# AFE_Only_ReplacedDischarge.net
KiCad netlist of a schematic drawn in EAGLE
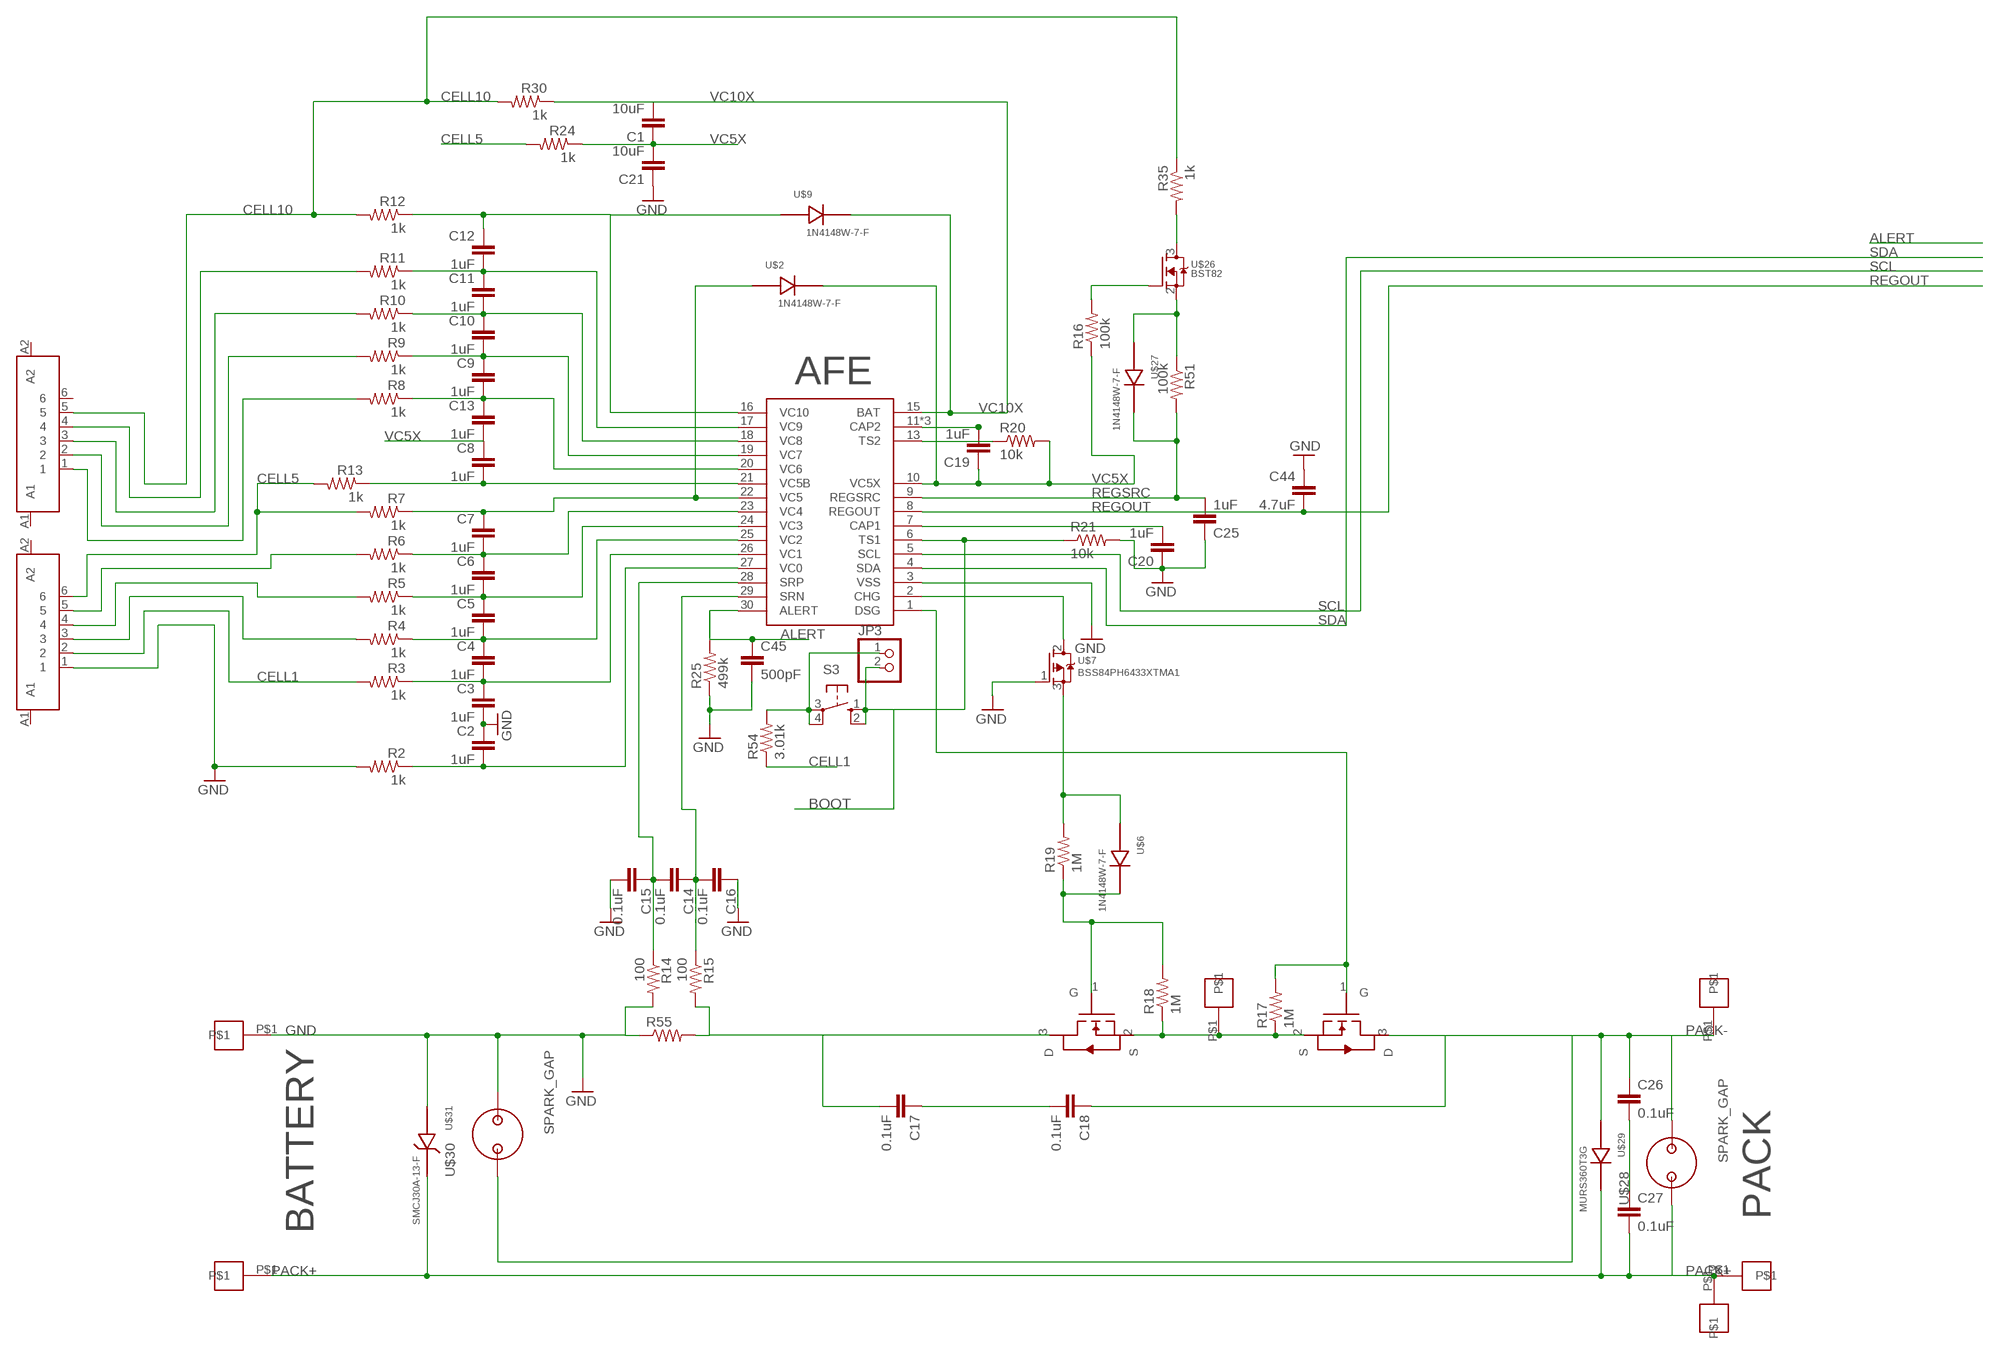
[diagram p0: schematic, sheet 1]
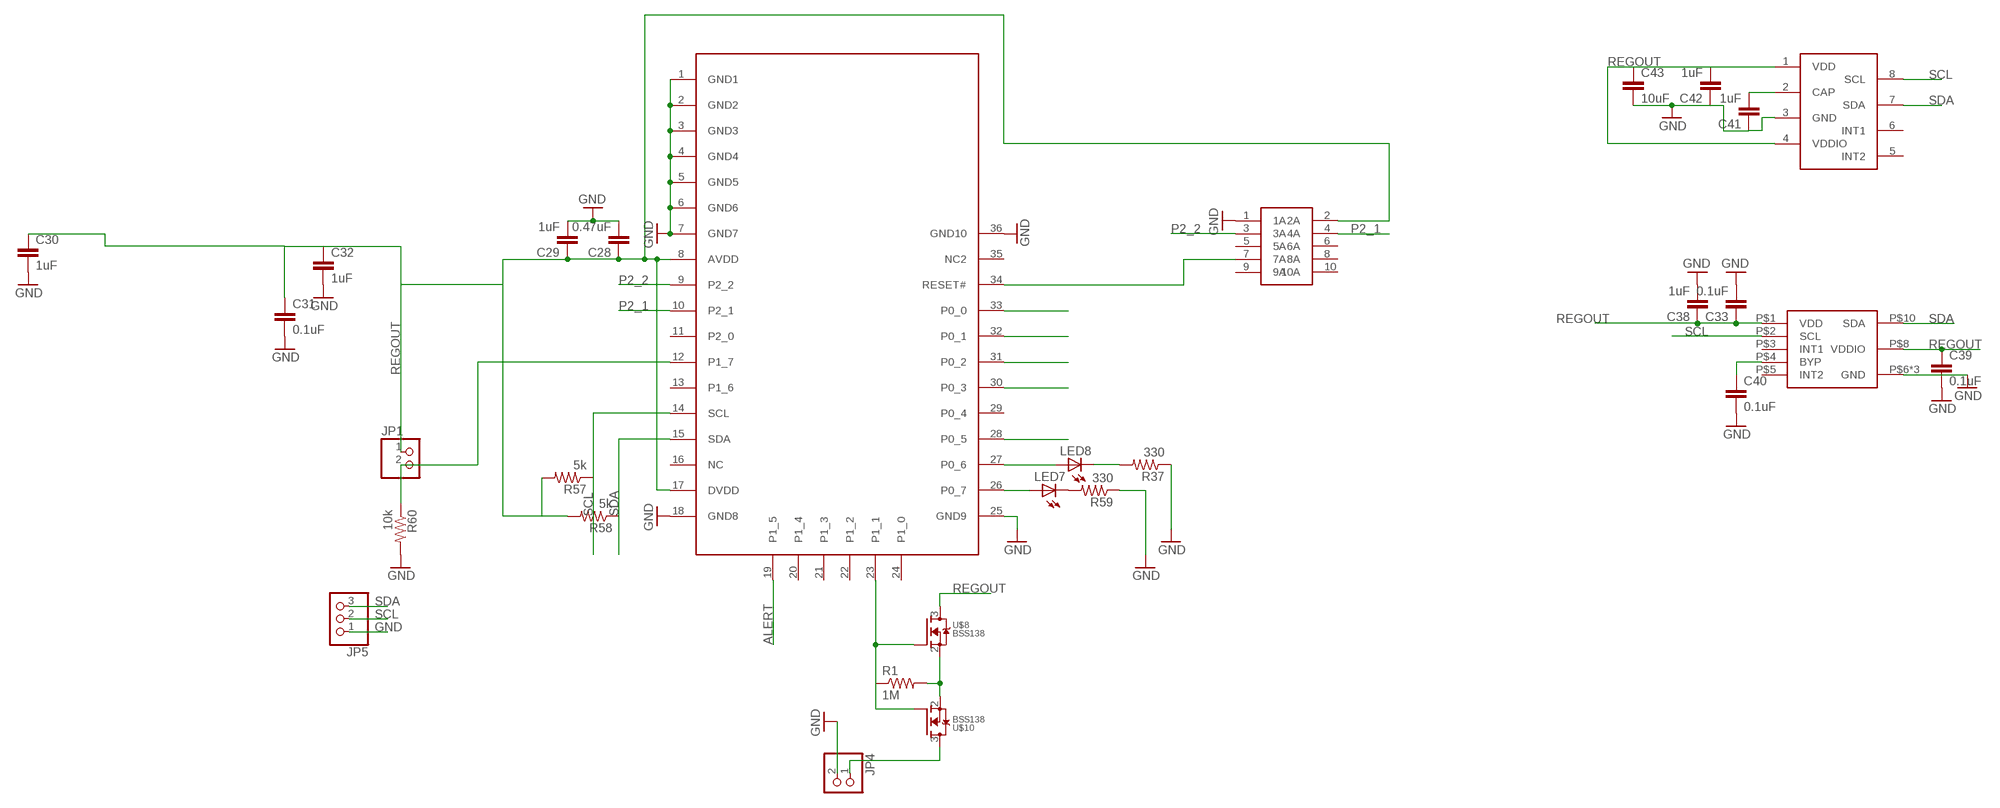
[diagram p1: schematic, sheet 2]

(export (version "E")
  (design (tool "Eeschema 10.0.6"))
  (components
    (comp (ref "C28")
      (value "0.47uF")
      (footprint "eagle-import:C0402")
      (libsource (lib "eagle-import") (part "C-EUC0402"))
    )
    (comp (ref "C29")
      (value "1uF")
      (footprint "eagle-import:C0402")
      (libsource (lib "eagle-import") (part "C-EUC0402"))
    )
    (comp (ref "C30")
      (value "1uF")
      (footprint "eagle-import:C0402")
      (libsource (lib "eagle-import") (part "C-EUC0402"))
    )
    (comp (ref "C31")
      (value "0.1uF")
      (footprint "eagle-import:C0402")
      (libsource (lib "eagle-import") (part "C-EUC0402"))
    )
    (comp (ref "C32")
      (value "1uF")
      (footprint "eagle-import:C0402")
      (libsource (lib "eagle-import") (part "C-EUC0402"))
    )
    (comp (ref "C33")
      (value "0.1uF")
      (footprint "eagle-import:C0402")
      (libsource (lib "eagle-import") (part "C-EUC0402"))
    )
    (comp (ref "C38")
      (value "1uF")
      (footprint "eagle-import:C0402")
      (libsource (lib "eagle-import") (part "C-EUC0402"))
    )
    (comp (ref "C39")
      (value "0.1uF")
      (footprint "eagle-import:C0402")
      (libsource (lib "eagle-import") (part "C-EUC0402"))
    )
    (comp (ref "C40")
      (value "0.1uF")
      (footprint "eagle-import:C0402")
      (libsource (lib "eagle-import") (part "C-EUC0402"))
    )
    (comp (ref "C41")
      (value "1uF")
      (footprint "eagle-import:C0402")
      (libsource (lib "eagle-import") (part "C-EUC0402"))
    )
    (comp (ref "C42")
      (value "1uF")
      (footprint "eagle-import:C0402")
      (libsource (lib "eagle-import") (part "C-EUC0402"))
    )
    (comp (ref "C43")
      (value "10uF")
      (footprint "eagle-import:C0603")
      (libsource (lib "eagle-import") (part "C-EUC0603"))
    )
    (comp (ref "JP1")
      (value "PINHD-1X2")
      (footprint "eagle-import:1X02")
      (libsource (lib "eagle-import") (part "PINHD-1X2"))
    )
    (comp (ref "JP4")
      (value "PINHD-1X2")
      (footprint "eagle-import:1X02")
      (libsource (lib "eagle-import") (part "PINHD-1X2"))
    )
    (comp (ref "JP5")
      (value "PINHD-1X3")
      (footprint "eagle-import:1X03")
      (libsource (lib "eagle-import") (part "PINHD-1X3"))
    )
    (comp (ref "LED7")
      (value "LEDCHIP-LED0603")
      (footprint "eagle-import:CHIP-LED0603")
      (libsource (lib "eagle-import") (part "LEDCHIP-LED0603"))
    )
    (comp (ref "LED8")
      (value "LEDCHIP-LED0603")
      (footprint "eagle-import:CHIP-LED0603")
      (libsource (lib "eagle-import") (part "LEDCHIP-LED0603"))
    )
    (comp (ref "R1")
      (value "1M")
      (footprint "eagle-import:R0402")
      (libsource (lib "eagle-import") (part "R-US_R0402"))
    )
    (comp (ref "R37")
      (value "330")
      (footprint "eagle-import:R0402")
      (libsource (lib "eagle-import") (part "R-US_R0402"))
    )
    (comp (ref "R57")
      (value "5k")
      (footprint "eagle-import:R0402")
      (libsource (lib "eagle-import") (part "R-US_R0402"))
    )
    (comp (ref "R58")
      (value "5k")
      (footprint "eagle-import:R0402")
      (libsource (lib "eagle-import") (part "R-US_R0402"))
    )
    (comp (ref "R59")
      (value "330")
      (footprint "eagle-import:R0402")
      (libsource (lib "eagle-import") (part "R-US_R0402"))
    )
    (comp (ref "R60")
      (value "10k")
      (footprint "eagle-import:R0402")
      (libsource (lib "eagle-import") (part "R-US_R0402"))
    )
    (comp (ref "U$8")
      (value "BSS138")
      (footprint "eagle-import:SOT23-3")
      (libsource (lib "eagle-import") (part "BSS138"))
    )
    (comp (ref "U$10")
      (value "BSS138")
      (footprint "eagle-import:SOT23-3")
      (libsource (lib "eagle-import") (part "BSS138"))
    )
    (comp (ref "U$20")
      (value "BLE113")
      (footprint "eagle-import:BLUEGIGA")
      (libsource (lib "eagle-import") (part "BLE113"))
    )
    (comp (ref "U$22")
      (value "RIBBON_10POS_MALE")
      (footprint "eagle-import:RIBBON_10POS_MALE")
      (libsource (lib "eagle-import") (part "RIBBON_10POS_MALE"))
    )
    (comp (ref "U$25")
      (value "MLP3115A2")
      (footprint "eagle-import:MLP3115A2")
      (libsource (lib "eagle-import") (part "MLP3115A2"))
    )
    (comp (ref "U$32")
      (value "MMA8653FC")
      (footprint "eagle-import:10-DFN2X2")
      (libsource (lib "eagle-import") (part "MMA8653FC"))
    )
    (comp (ref "C1")
      (value "10uF")
      (footprint "eagle-import:C1210")
      (libsource (lib "eagle-import") (part "C-EUC1210"))
    )
    (comp (ref "C2")
      (value "1uF")
      (footprint "eagle-import:C0805")
      (libsource (lib "eagle-import") (part "C-EUC0805"))
    )
    (comp (ref "C3")
      (value "1uF")
      (footprint "eagle-import:C0805")
      (libsource (lib "eagle-import") (part "C-EUC0805"))
    )
    (comp (ref "C4")
      (value "1uF")
      (footprint "eagle-import:C0805")
      (libsource (lib "eagle-import") (part "C-EUC0805"))
    )
    (comp (ref "C5")
      (value "1uF")
      (footprint "eagle-import:C0805")
      (libsource (lib "eagle-import") (part "C-EUC0805"))
    )
    (comp (ref "C6")
      (value "1uF")
      (footprint "eagle-import:C0805")
      (libsource (lib "eagle-import") (part "C-EUC0805"))
    )
    (comp (ref "C7")
      (value "1uF")
      (footprint "eagle-import:C0805")
      (libsource (lib "eagle-import") (part "C-EUC0805"))
    )
    (comp (ref "C8")
      (value "1uF")
      (footprint "eagle-import:C0805")
      (libsource (lib "eagle-import") (part "C-EUC0805"))
    )
    (comp (ref "C9")
      (value "1uF")
      (footprint "eagle-import:C0805")
      (libsource (lib "eagle-import") (part "C-EUC0805"))
    )
    (comp (ref "C10")
      (value "1uF")
      (footprint "eagle-import:C0805")
      (libsource (lib "eagle-import") (part "C-EUC0805"))
    )
    (comp (ref "C11")
      (value "1uF")
      (footprint "eagle-import:C0805")
      (libsource (lib "eagle-import") (part "C-EUC0805"))
    )
    (comp (ref "C12")
      (value "1uF")
      (footprint "eagle-import:C0805")
      (libsource (lib "eagle-import") (part "C-EUC0805"))
    )
    (comp (ref "C13")
      (value "1uF")
      (footprint "eagle-import:C0805")
      (libsource (lib "eagle-import") (part "C-EUC0805"))
    )
    (comp (ref "C14")
      (value "0.1uF")
      (footprint "eagle-import:C0805")
      (libsource (lib "eagle-import") (part "C-EUC0805"))
    )
    (comp (ref "C15")
      (value "0.1uF")
      (footprint "eagle-import:C0805")
      (libsource (lib "eagle-import") (part "C-EUC0805"))
    )
    (comp (ref "C16")
      (value "0.1uF")
      (footprint "eagle-import:C0805")
      (libsource (lib "eagle-import") (part "C-EUC0805"))
    )
    (comp (ref "C17")
      (value "0.1uF")
      (footprint "eagle-import:C0805")
      (libsource (lib "eagle-import") (part "C-EUC0805"))
    )
    (comp (ref "C18")
      (value "0.1uF")
      (footprint "eagle-import:C0805")
      (libsource (lib "eagle-import") (part "C-EUC0805"))
    )
    (comp (ref "C19")
      (value "1uF")
      (footprint "eagle-import:C0805")
      (libsource (lib "eagle-import") (part "C-EUC0805"))
    )
    (comp (ref "C20")
      (value "1uF")
      (footprint "eagle-import:C0805")
      (libsource (lib "eagle-import") (part "C-EUC0805"))
    )
    (comp (ref "C21")
      (value "10uF")
      (footprint "eagle-import:C1210")
      (libsource (lib "eagle-import") (part "C-EUC1210"))
    )
    (comp (ref "C25")
      (value "1uF")
      (footprint "eagle-import:C0805")
      (libsource (lib "eagle-import") (part "C-EUC0805"))
    )
    (comp (ref "C26")
      (value "0.1uF")
      (footprint "eagle-import:C0805")
      (libsource (lib "eagle-import") (part "C-EUC0805"))
    )
    (comp (ref "C27")
      (value "0.1uF")
      (footprint "eagle-import:C0805")
      (libsource (lib "eagle-import") (part "C-EUC0805"))
    )
    (comp (ref "C44")
      (value "4.7uF")
      (footprint "eagle-import:C0805")
      (libsource (lib "eagle-import") (part "C-EUC0805"))
    )
    (comp (ref "C45")
      (value "500pF")
      (footprint "eagle-import:C0603")
      (libsource (lib "eagle-import") (part "C-EUC0603"))
    )
    (comp (ref "JP3")
      (value "PINHD-1X2")
      (footprint "eagle-import:1X02")
      (libsource (lib "eagle-import") (part "PINHD-1X2"))
    )
    (comp (ref "R2")
      (value "1k")
      (footprint "eagle-import:R1206")
      (libsource (lib "eagle-import") (part "R-US_R1206"))
    )
    (comp (ref "R3")
      (value "1k")
      (footprint "eagle-import:R1206")
      (libsource (lib "eagle-import") (part "R-US_R1206"))
    )
    (comp (ref "R4")
      (value "1k")
      (footprint "eagle-import:R1206")
      (libsource (lib "eagle-import") (part "R-US_R1206"))
    )
    (comp (ref "R5")
      (value "1k")
      (footprint "eagle-import:R1206")
      (libsource (lib "eagle-import") (part "R-US_R1206"))
    )
    (comp (ref "R6")
      (value "1k")
      (footprint "eagle-import:R1206")
      (libsource (lib "eagle-import") (part "R-US_R1206"))
    )
    (comp (ref "R7")
      (value "1k")
      (footprint "eagle-import:R1206")
      (libsource (lib "eagle-import") (part "R-US_R1206"))
    )
    (comp (ref "R8")
      (value "1k")
      (footprint "eagle-import:R1206")
      (libsource (lib "eagle-import") (part "R-US_R1206"))
    )
    (comp (ref "R9")
      (value "1k")
      (footprint "eagle-import:R1206")
      (libsource (lib "eagle-import") (part "R-US_R1206"))
    )
    (comp (ref "R10")
      (value "1k")
      (footprint "eagle-import:R1206")
      (libsource (lib "eagle-import") (part "R-US_R1206"))
    )
    (comp (ref "R11")
      (value "1k")
      (footprint "eagle-import:R1206")
      (libsource (lib "eagle-import") (part "R-US_R1206"))
    )
    (comp (ref "R12")
      (value "1k")
      (footprint "eagle-import:R1206")
      (libsource (lib "eagle-import") (part "R-US_R1206"))
    )
    (comp (ref "R13")
      (value "1k")
      (footprint "eagle-import:R1206")
      (libsource (lib "eagle-import") (part "R-US_R1206"))
    )
    (comp (ref "R14")
      (value "100")
      (footprint "eagle-import:R0805")
      (libsource (lib "eagle-import") (part "R-US_R0805"))
    )
    (comp (ref "R15")
      (value "100")
      (footprint "eagle-import:R0805")
      (libsource (lib "eagle-import") (part "R-US_R0805"))
    )
    (comp (ref "R16")
      (value "100k")
      (footprint "eagle-import:R0805")
      (libsource (lib "eagle-import") (part "R-US_R0805"))
    )
    (comp (ref "R17")
      (value "1M")
      (footprint "eagle-import:R1206")
      (libsource (lib "eagle-import") (part "R-US_R1206"))
    )
    (comp (ref "R18")
      (value "1M")
      (footprint "eagle-import:R1206")
      (libsource (lib "eagle-import") (part "R-US_R1206"))
    )
    (comp (ref "R19")
      (value "1M")
      (footprint "eagle-import:R1206")
      (libsource (lib "eagle-import") (part "R-US_R1206"))
    )
    (comp (ref "R20")
      (value "10k")
      (footprint "eagle-import:R0805")
      (libsource (lib "eagle-import") (part "R-US_R0805"))
    )
    (comp (ref "R21")
      (value "10k")
      (footprint "eagle-import:R0805")
      (libsource (lib "eagle-import") (part "R-US_R0805"))
    )
    (comp (ref "R24")
      (value "1k")
      (footprint "eagle-import:R1206")
      (libsource (lib "eagle-import") (part "R-US_R1206"))
    )
    (comp (ref "R25")
      (value "499k")
      (footprint "eagle-import:R0603")
      (libsource (lib "eagle-import") (part "R-US_R0603"))
    )
    (comp (ref "R30")
      (value "1k")
      (footprint "eagle-import:R1206")
      (libsource (lib "eagle-import") (part "R-US_R1206"))
    )
    (comp (ref "R35")
      (value "1k")
      (footprint "eagle-import:R1206")
      (libsource (lib "eagle-import") (part "R-US_R1206"))
    )
    (comp (ref "R51")
      (value "100k")
      (footprint "eagle-import:R0805")
      (libsource (lib "eagle-import") (part "R-US_R0805"))
    )
    (comp (ref "R54")
      (value "3.01k")
      (footprint "eagle-import:R1206")
      (libsource (lib "eagle-import") (part "R-US_R1206"))
    )
    (comp (ref "R55")
      (value "R-US_R2512")
      (footprint "eagle-import:R2512")
      (libsource (lib "eagle-import") (part "R-US_R2512"))
    )
    (comp (ref "S3")
      (value "10-XX")
      (footprint "eagle-import:B3F-10XX")
      (fields (field (name "MPN") "B3F-1000"))
      (libsource (lib "eagle-import") (part "10-XX"))
    )
    (comp (ref "U$1")
      (value "BQ76930")
      (footprint "eagle-import:SOIC-30")
      (libsource (lib "eagle-import") (part "BQ76930"))
    )
    (comp (ref "U$2")
      (value "1N4148W-7-F")
      (footprint "eagle-import:SOD-123")
      (libsource (lib "eagle-import") (part "1N4148W-7-F"))
    )
    (comp (ref "U$3")
      (value "PAD")
      (footprint "eagle-import:PAD")
      (libsource (lib "eagle-import") (part "PAD"))
    )
    (comp (ref "U$4")
      (value "AOB290L")
      (footprint "eagle-import:TO-263")
      (libsource (lib "eagle-import") (part "AOB290L"))
    )
    (comp (ref "U$5")
      (value "AOB290L")
      (footprint "eagle-import:TO-263")
      (libsource (lib "eagle-import") (part "AOB290L"))
    )
    (comp (ref "U$6")
      (value "1N4148W-7-F")
      (footprint "eagle-import:SOD-123")
      (libsource (lib "eagle-import") (part "1N4148W-7-F"))
    )
    (comp (ref "U$7")
      (value "BSS84PH6433XTMA1")
      (footprint "eagle-import:SOT23-3")
      (libsource (lib "eagle-import") (part "BSS84PH6433XTMA1"))
    )
    (comp (ref "U$9")
      (value "1N4148W-7-F")
      (footprint "eagle-import:SOD-123")
      (libsource (lib "eagle-import") (part "1N4148W-7-F"))
    )
    (comp (ref "U$24")
      (value "JST_6PIN")
      (footprint "eagle-import:JST_6PIN")
      (libsource (lib "eagle-import") (part "JST_6PIN"))
    )
    (comp (ref "U$26")
      (value "BST82")
      (footprint "eagle-import:SOT23-3")
      (libsource (lib "eagle-import") (part "BST82"))
    )
    (comp (ref "U$27")
      (value "1N4148W-7-F")
      (footprint "eagle-import:SOD-123")
      (libsource (lib "eagle-import") (part "1N4148W-7-F"))
    )
    (comp (ref "U$28")
      (value "SPARK_GAP")
      (footprint "eagle-import:SPARK_GAP")
      (libsource (lib "eagle-import") (part "SPARK_GAP"))
    )
    (comp (ref "U$29")
      (value "MURS360T3G")
      (footprint "eagle-import:SMC(DO-214AB)")
      (libsource (lib "eagle-import") (part "MURS360T3G"))
    )
    (comp (ref "U$30")
      (value "SPARK_GAP")
      (footprint "eagle-import:SPARK_GAP")
      (libsource (lib "eagle-import") (part "SPARK_GAP"))
    )
    (comp (ref "U$31")
      (value "SMCJ30A-13-F")
      (footprint "eagle-import:SMB(DO-214AA)")
      (libsource (lib "eagle-import") (part "SMCJ30A-13-F"))
    )
    (comp (ref "U$33")
      (value "JST_6PIN")
      (footprint "eagle-import:JST_6PIN")
      (libsource (lib "eagle-import") (part "JST_6PIN"))
    )
    (comp (ref "U$35")
      (value "PAD")
      (footprint "eagle-import:PAD")
      (libsource (lib "eagle-import") (part "PAD"))
    )
    (comp (ref "U$36")
      (value "PAD")
      (footprint "eagle-import:PAD")
      (libsource (lib "eagle-import") (part "PAD"))
    )
    (comp (ref "U$37")
      (value "PAD")
      (footprint "eagle-import:PAD")
      (libsource (lib "eagle-import") (part "PAD"))
    )
    (comp (ref "U$38")
      (value "PAD")
      (footprint "eagle-import:PAD")
      (libsource (lib "eagle-import") (part "PAD"))
    )
    (comp (ref "U$39")
      (value "PAD")
      (footprint "eagle-import:PAD")
      (libsource (lib "eagle-import") (part "PAD"))
    )
  )
  (nets
    (net (code "1") (name "ALERT") (class "Default")
      (node (ref "C45") (pin "1") (pinfunction "1_1") (pintype "passive"))
      (node (ref "R25") (pin "2") (pinfunction "2_2") (pintype "passive"))
      (node (ref "U$1") (pin "30") (pinfunction "ALERT_30") (pintype "bidirectional"))
      (node (ref "U$20") (pin "19") (pinfunction "P1_5_19") (pintype "bidirectional"))
    )
    (net (code "2") (name "BOOT") (class "Default")
      (node (ref "JP3") (pin "2") (pinfunction "2_2") (pintype "passive"))
      (node (ref "R21") (pin "1") (pinfunction "1_1") (pintype "passive"))
      (node (ref "S3") (pin "1") (pinfunction "S_1") (pintype "passive"))
      (node (ref "S3") (pin "2") (pinfunction "S1_2") (pintype "passive"))
      (node (ref "U$1") (pin "6") (pinfunction "TS1_6") (pintype "bidirectional"))
    )
    (net (code "3") (name "CELL1") (class "Default")
      (node (ref "R3") (pin "2") (pinfunction "2_2") (pintype "passive"))
      (node (ref "R54") (pin "1") (pinfunction "1_1") (pintype "passive"))
      (node (ref "U$33") (pin "2") (pinfunction "2_2") (pintype "bidirectional"))
    )
    (net (code "4") (name "CELL5") (class "Default")
      (node (ref "R13") (pin "2") (pinfunction "2_2") (pintype "passive"))
      (node (ref "R24") (pin "2") (pinfunction "2_2") (pintype "passive"))
      (node (ref "R7") (pin "2") (pinfunction "2_2") (pintype "passive"))
      (node (ref "U$33") (pin "6") (pinfunction "6_6") (pintype "bidirectional"))
    )
    (net (code "5") (name "CELL10") (class "Default")
      (node (ref "R12") (pin "2") (pinfunction "2_2") (pintype "passive"))
      (node (ref "R30") (pin "2") (pinfunction "2_2") (pintype "passive"))
      (node (ref "R35") (pin "1") (pinfunction "1_1") (pintype "passive"))
      (node (ref "U$24") (pin "5") (pinfunction "5_5") (pintype "bidirectional"))
    )
    (net (code "6") (name "GND") (class "Default")
      (node (ref "C15") (pin "2") (pinfunction "2_2") (pintype "passive"))
      (node (ref "C16") (pin "1") (pinfunction "1_1") (pintype "passive"))
      (node (ref "C2") (pin "1") (pinfunction "1_1") (pintype "passive"))
      (node (ref "C20") (pin "1") (pinfunction "1_1") (pintype "passive"))
      (node (ref "C21") (pin "1") (pinfunction "1_1") (pintype "passive"))
      (node (ref "C25") (pin "1") (pinfunction "1_1") (pintype "passive"))
      (node (ref "C28") (pin "2") (pinfunction "2_2") (pintype "passive"))
      (node (ref "C29") (pin "2") (pinfunction "2_2") (pintype "passive"))
      (node (ref "C3") (pin "2") (pinfunction "2_2") (pintype "passive"))
      (node (ref "C30") (pin "2") (pinfunction "2_2") (pintype "passive"))
      (node (ref "C31") (pin "2") (pinfunction "2_2") (pintype "passive"))
      (node (ref "C32") (pin "2") (pinfunction "2_2") (pintype "passive"))
      (node (ref "C33") (pin "2") (pinfunction "2_2") (pintype "passive"))
      (node (ref "C38") (pin "2") (pinfunction "2_2") (pintype "passive"))
      (node (ref "C39") (pin "2") (pinfunction "2_2") (pintype "passive"))
      (node (ref "C40") (pin "2") (pinfunction "2_2") (pintype "passive"))
      (node (ref "C41") (pin "1") (pinfunction "1_1") (pintype "passive"))
      (node (ref "C42") (pin "1") (pinfunction "1_1") (pintype "passive"))
      (node (ref "C43") (pin "2") (pinfunction "2_2") (pintype "passive"))
      (node (ref "C44") (pin "1") (pinfunction "1_1") (pintype "passive"))
      (node (ref "C45") (pin "2") (pinfunction "2_2") (pintype "passive"))
      (node (ref "JP4") (pin "2") (pinfunction "2_2") (pintype "passive"))
      (node (ref "JP5") (pin "1") (pinfunction "1_1") (pintype "passive"))
      (node (ref "R14") (pin "2") (pinfunction "2_2") (pintype "passive"))
      (node (ref "R2") (pin "2") (pinfunction "2_2") (pintype "passive"))
      (node (ref "R21") (pin "2") (pinfunction "2_2") (pintype "passive"))
      (node (ref "R25") (pin "1") (pinfunction "1_1") (pintype "passive"))
      (node (ref "R37") (pin "1") (pinfunction "1_1") (pintype "passive"))
      (node (ref "R55") (pin "1") (pinfunction "1_1") (pintype "passive"))
      (node (ref "R59") (pin "1") (pinfunction "1_1") (pintype "passive"))
      (node (ref "R60") (pin "2") (pinfunction "2_2") (pintype "passive"))
      (node (ref "U$1") (pin "3") (pinfunction "VSS_3") (pintype "bidirectional"))
      (node (ref "U$20") (pin "1") (pinfunction "GND1_1") (pintype "bidirectional"))
      (node (ref "U$20") (pin "18") (pinfunction "GND8_18") (pintype "bidirectional"))
      (node (ref "U$20") (pin "2") (pinfunction "GND2_2") (pintype "bidirectional"))
      (node (ref "U$20") (pin "25") (pinfunction "GND9_25") (pintype "bidirectional"))
      (node (ref "U$20") (pin "3") (pinfunction "GND3_3") (pintype "bidirectional"))
      (node (ref "U$20") (pin "36") (pinfunction "GND10_36") (pintype "bidirectional"))
      (node (ref "U$20") (pin "4") (pinfunction "GND4_4") (pintype "bidirectional"))
      (node (ref "U$20") (pin "5") (pinfunction "GND5_5") (pintype "bidirectional"))
      (node (ref "U$20") (pin "6") (pinfunction "GND6_6") (pintype "bidirectional"))
      (node (ref "U$20") (pin "7") (pinfunction "GND7_7") (pintype "bidirectional"))
      (node (ref "U$22") (pin "1") (pinfunction "1A_1") (pintype "bidirectional"))
      (node (ref "U$25") (pin "3") (pinfunction "GND_3") (pintype "bidirectional"))
      (node (ref "U$3") (pin "P$1") (pinfunction "P$1_P$1") (pintype "bidirectional"))
      (node (ref "U$30") (pin "P$2") (pinfunction "P$2_P$2") (pintype "bidirectional"))
      (node (ref "U$31") (pin "P$1") (pinfunction "1_P$1") (pintype "bidirectional"))
      (node (ref "U$32") (pin "P$6") (pinfunction "GND_P$6") (pintype "bidirectional"))
      (node (ref "U$32") (pin "P$7") (pinfunction "GND_P$7") (pintype "bidirectional"))
      (node (ref "U$32") (pin "P$9") (pinfunction "GND_P$9") (pintype "bidirectional"))
      (node (ref "U$33") (pin "1") (pinfunction "1_1") (pintype "bidirectional"))
      (node (ref "U$7") (pin "1") (pinfunction "G_1") (pintype "bidirectional"))
    )
    (net (code "7") (name "Net-(C17-Pad1)") (class "Default")
      (node (ref "C17") (pin "1") (pinfunction "1_1") (pintype "passive"))
      (node (ref "C18") (pin "2") (pinfunction "2_2") (pintype "passive"))
    )
    (net (code "8") (name "Net-(C19-Pad2)") (class "Default")
      (node (ref "C19") (pin "2") (pinfunction "2_2") (pintype "passive"))
      (node (ref "U$1") (pin "11") (pinfunction "CAP2_11") (pintype "bidirectional"))
      (node (ref "U$1") (pin "12") (pinfunction "CAP2_12") (pintype "bidirectional"))
      (node (ref "U$1") (pin "14") (pinfunction "CAP2_14") (pintype "bidirectional"))
    )
    (net (code "9") (name "Net-(C26-Pad2)") (class "Default")
      (node (ref "C26") (pin "2") (pinfunction "2_2") (pintype "passive"))
      (node (ref "C27") (pin "1") (pinfunction "1_1") (pintype "passive"))
    )
    (net (code "10") (name "Net-(LED7-PadC)") (class "Default")
      (node (ref "LED7") (pin "C") (pinfunction "C_C") (pintype "passive"))
      (node (ref "R59") (pin "2") (pinfunction "2_2") (pintype "passive"))
    )
    (net (code "11") (name "Net-(LED8-PadC)") (class "Default")
      (node (ref "LED8") (pin "C") (pinfunction "C_C") (pintype "passive"))
      (node (ref "R37") (pin "2") (pinfunction "2_2") (pintype "passive"))
    )
    (net (code "12") (name "Net-(R4-Pad2)") (class "Default")
      (node (ref "R4") (pin "2") (pinfunction "2_2") (pintype "passive"))
      (node (ref "U$33") (pin "3") (pinfunction "3_3") (pintype "bidirectional"))
    )
    (net (code "13") (name "Net-(R5-Pad2)") (class "Default")
      (node (ref "R5") (pin "2") (pinfunction "2_2") (pintype "passive"))
      (node (ref "U$33") (pin "4") (pinfunction "4_4") (pintype "bidirectional"))
    )
    (net (code "14") (name "Net-(R6-Pad2)") (class "Default")
      (node (ref "R6") (pin "2") (pinfunction "2_2") (pintype "passive"))
      (node (ref "U$33") (pin "5") (pinfunction "5_5") (pintype "bidirectional"))
    )
    (net (code "15") (name "Net-(R8-Pad2)") (class "Default")
      (node (ref "R8") (pin "2") (pinfunction "2_2") (pintype "passive"))
      (node (ref "U$24") (pin "1") (pinfunction "1_1") (pintype "bidirectional"))
    )
    (net (code "16") (name "Net-(R9-Pad2)") (class "Default")
      (node (ref "R9") (pin "2") (pinfunction "2_2") (pintype "passive"))
      (node (ref "U$24") (pin "2") (pinfunction "2_2") (pintype "bidirectional"))
    )
    (net (code "17") (name "Net-(R10-Pad2)") (class "Default")
      (node (ref "R10") (pin "2") (pinfunction "2_2") (pintype "passive"))
      (node (ref "U$24") (pin "3") (pinfunction "3_3") (pintype "bidirectional"))
    )
    (net (code "18") (name "Net-(R11-Pad2)") (class "Default")
      (node (ref "R11") (pin "2") (pinfunction "2_2") (pintype "passive"))
      (node (ref "U$24") (pin "4") (pinfunction "4_4") (pintype "bidirectional"))
    )
    (net (code "19") (name "Net-(S3-P)") (class "Default")
      (node (ref "JP3") (pin "1") (pinfunction "1_1") (pintype "passive"))
      (node (ref "R54") (pin "2") (pinfunction "2_2") (pintype "passive"))
      (node (ref "S3") (pin "3") (pinfunction "P_3") (pintype "passive"))
      (node (ref "S3") (pin "4") (pinfunction "P1_4") (pintype "passive"))
    )
    (net (code "20") (name "Net-(U$1-CAP1)") (class "Default")
      (node (ref "C20") (pin "2") (pinfunction "2_2") (pintype "passive"))
      (node (ref "U$1") (pin "7") (pinfunction "CAP1_7") (pintype "bidirectional"))
    )
    (net (code "21") (name "Net-(U$1-CHG)") (class "Default")
      (node (ref "U$1") (pin "2") (pinfunction "CHG_2") (pintype "bidirectional"))
      (node (ref "U$7") (pin "2") (pinfunction "S_2") (pintype "bidirectional"))
    )
    (net (code "22") (name "Net-(U$1-DSG)") (class "Default")
      (node (ref "R17") (pin "2") (pinfunction "2_2") (pintype "passive"))
      (node (ref "U$1") (pin "1") (pinfunction "DSG_1") (pintype "bidirectional"))
      (node (ref "U$4") (pin "1") (pinfunction "G_1") (pintype "bidirectional"))
    )
    (net (code "23") (name "Net-(U$1-SRN)") (class "Default")
      (node (ref "C14") (pin "1") (pinfunction "1_1") (pintype "passive"))
      (node (ref "C16") (pin "2") (pinfunction "2_2") (pintype "passive"))
      (node (ref "R15") (pin "1") (pinfunction "1_1") (pintype "passive"))
      (node (ref "U$1") (pin "29") (pinfunction "SRN_29") (pintype "bidirectional"))
    )
    (net (code "24") (name "Net-(U$1-SRP)") (class "Default")
      (node (ref "C14") (pin "2") (pinfunction "2_2") (pintype "passive"))
      (node (ref "C15") (pin "1") (pinfunction "1_1") (pintype "passive"))
      (node (ref "R14") (pin "1") (pinfunction "1_1") (pintype "passive"))
      (node (ref "U$1") (pin "28") (pinfunction "SRP_28") (pintype "bidirectional"))
    )
    (net (code "25") (name "Net-(U$1-TS2)") (class "Default")
      (node (ref "R20") (pin "1") (pinfunction "1_1") (pintype "passive"))
      (node (ref "U$1") (pin "13") (pinfunction "TS2_13") (pintype "bidirectional"))
    )
    (net (code "26") (name "Net-(U$1-VC0)") (class "Default")
      (node (ref "C2") (pin "2") (pinfunction "2_2") (pintype "passive"))
      (node (ref "R2") (pin "1") (pinfunction "1_1") (pintype "passive"))
      (node (ref "U$1") (pin "27") (pinfunction "VC0_27") (pintype "bidirectional"))
    )
    (net (code "27") (name "Net-(U$1-VC1)") (class "Default")
      (node (ref "C3") (pin "1") (pinfunction "1_1") (pintype "passive"))
      (node (ref "C4") (pin "2") (pinfunction "2_2") (pintype "passive"))
      (node (ref "R3") (pin "1") (pinfunction "1_1") (pintype "passive"))
      (node (ref "U$1") (pin "26") (pinfunction "VC1_26") (pintype "bidirectional"))
    )
    (net (code "28") (name "Net-(U$1-VC2)") (class "Default")
      (node (ref "C4") (pin "1") (pinfunction "1_1") (pintype "passive"))
      (node (ref "C5") (pin "2") (pinfunction "2_2") (pintype "passive"))
      (node (ref "R4") (pin "1") (pinfunction "1_1") (pintype "passive"))
      (node (ref "U$1") (pin "25") (pinfunction "VC2_25") (pintype "bidirectional"))
    )
    (net (code "29") (name "Net-(U$1-VC3)") (class "Default")
      (node (ref "C5") (pin "1") (pinfunction "1_1") (pintype "passive"))
      (node (ref "C6") (pin "2") (pinfunction "2_2") (pintype "passive"))
      (node (ref "R5") (pin "1") (pinfunction "1_1") (pintype "passive"))
      (node (ref "U$1") (pin "24") (pinfunction "VC3_24") (pintype "bidirectional"))
    )
    (net (code "30") (name "Net-(U$1-VC4)") (class "Default")
      (node (ref "C6") (pin "1") (pinfunction "1_1") (pintype "passive"))
      (node (ref "C7") (pin "2") (pinfunction "2_2") (pintype "passive"))
      (node (ref "R6") (pin "1") (pinfunction "1_1") (pintype "passive"))
      (node (ref "U$1") (pin "23") (pinfunction "VC4_23") (pintype "bidirectional"))
    )
    (net (code "31") (name "Net-(U$1-VC5)") (class "Default")
      (node (ref "C7") (pin "1") (pinfunction "1_1") (pintype "passive"))
      (node (ref "R7") (pin "1") (pinfunction "1_1") (pintype "passive"))
      (node (ref "U$1") (pin "22") (pinfunction "VC5_22") (pintype "bidirectional"))
      (node (ref "U$2") (pin "P$1") (pinfunction "P$1_P$1") (pintype "bidirectional"))
    )
    (net (code "32") (name "Net-(U$1-VC5B)") (class "Default")
      (node (ref "C8") (pin "2") (pinfunction "2_2") (pintype "passive"))
      (node (ref "R13") (pin "1") (pinfunction "1_1") (pintype "passive"))
      (node (ref "U$1") (pin "21") (pinfunction "VC5B_21") (pintype "bidirectional"))
    )
    (net (code "33") (name "Net-(U$1-VC6)") (class "Default")
      (node (ref "C13") (pin "1") (pinfunction "1_1") (pintype "passive"))
      (node (ref "C9") (pin "2") (pinfunction "2_2") (pintype "passive"))
      (node (ref "R8") (pin "1") (pinfunction "1_1") (pintype "passive"))
      (node (ref "U$1") (pin "20") (pinfunction "VC6_20") (pintype "bidirectional"))
    )
    (net (code "34") (name "Net-(U$1-VC7)") (class "Default")
      (node (ref "C10") (pin "2") (pinfunction "2_2") (pintype "passive"))
      (node (ref "C9") (pin "1") (pinfunction "1_1") (pintype "passive"))
      (node (ref "R9") (pin "1") (pinfunction "1_1") (pintype "passive"))
      (node (ref "U$1") (pin "19") (pinfunction "VC7_19") (pintype "bidirectional"))
    )
    (net (code "35") (name "Net-(U$1-VC8)") (class "Default")
      (node (ref "C10") (pin "1") (pinfunction "1_1") (pintype "passive"))
      (node (ref "C11") (pin "2") (pinfunction "2_2") (pintype "passive"))
      (node (ref "R10") (pin "1") (pinfunction "1_1") (pintype "passive"))
      (node (ref "U$1") (pin "18") (pinfunction "VC8_18") (pintype "bidirectional"))
    )
    (net (code "36") (name "Net-(U$1-VC9)") (class "Default")
      (node (ref "C11") (pin "1") (pinfunction "1_1") (pintype "passive"))
      (node (ref "C12") (pin "2") (pinfunction "2_2") (pintype "passive"))
      (node (ref "R11") (pin "1") (pinfunction "1_1") (pintype "passive"))
      (node (ref "U$1") (pin "17") (pinfunction "VC9_17") (pintype "bidirectional"))
    )
    (net (code "37") (name "Net-(U$1-VC10)") (class "Default")
      (node (ref "C12") (pin "1") (pinfunction "1_1") (pintype "passive"))
      (node (ref "R12") (pin "1") (pinfunction "1_1") (pintype "passive"))
      (node (ref "U$1") (pin "16") (pinfunction "VC10_16") (pintype "bidirectional"))
      (node (ref "U$9") (pin "P$1") (pinfunction "P$1_P$1") (pintype "bidirectional"))
    )
    (net (code "38") (name "Net-(U$4-S)") (class "Default")
      (node (ref "R17") (pin "1") (pinfunction "1_1") (pintype "passive"))
      (node (ref "R18") (pin "1") (pinfunction "1_1") (pintype "passive"))
      (node (ref "U$37") (pin "P$1") (pinfunction "P$1_P$1") (pintype "bidirectional"))
      (node (ref "U$4") (pin "2") (pinfunction "S_2") (pintype "bidirectional"))
      (node (ref "U$5") (pin "2") (pinfunction "S_2") (pintype "bidirectional"))
    )
    (net (code "39") (name "Net-(U$5-D)") (class "Default")
      (node (ref "C17") (pin "2") (pinfunction "2_2") (pintype "passive"))
      (node (ref "R15") (pin "2") (pinfunction "2_2") (pintype "passive"))
      (node (ref "R55") (pin "2") (pinfunction "2_2") (pintype "passive"))
      (node (ref "U$5") (pin "3") (pinfunction "D_3") (pintype "bidirectional"))
    )
    (net (code "40") (name "Net-(U$5-G)") (class "Default")
      (node (ref "R18") (pin "2") (pinfunction "2_2") (pintype "passive"))
      (node (ref "R19") (pin "1") (pinfunction "1_1") (pintype "passive"))
      (node (ref "U$5") (pin "1") (pinfunction "G_1") (pintype "bidirectional"))
      (node (ref "U$6") (pin "P$2") (pinfunction "P$2_P$2") (pintype "bidirectional"))
    )
    (net (code "41") (name "Net-(U$7-D)") (class "Default")
      (node (ref "R19") (pin "2") (pinfunction "2_2") (pintype "passive"))
      (node (ref "U$6") (pin "P$1") (pinfunction "P$1_P$1") (pintype "bidirectional"))
      (node (ref "U$7") (pin "3") (pinfunction "D_3") (pintype "bidirectional"))
    )
    (net (code "42") (name "Net-(U$10-D)") (class "Default")
      (node (ref "JP4") (pin "1") (pinfunction "1_1") (pintype "passive"))
      (node (ref "U$10") (pin "3") (pinfunction "D_3") (pintype "bidirectional"))
    )
    (net (code "43") (name "Net-(U$10-G)") (class "Default")
      (node (ref "R1") (pin "1") (pinfunction "1_1") (pintype "passive"))
      (node (ref "U$10") (pin "1") (pinfunction "G_1") (pintype "bidirectional"))
      (node (ref "U$20") (pin "23") (pinfunction "P1_1_23") (pintype "bidirectional"))
      (node (ref "U$8") (pin "1") (pinfunction "G_1") (pintype "bidirectional"))
    )
    (net (code "44") (name "Net-(U$10-S)") (class "Default")
      (node (ref "R1") (pin "2") (pinfunction "2_2") (pintype "passive"))
      (node (ref "U$10") (pin "2") (pinfunction "S_2") (pintype "bidirectional"))
      (node (ref "U$8") (pin "2") (pinfunction "S_2") (pintype "bidirectional"))
    )
    (net (code "45") (name "Net-(U$20-P0_6)") (class "Default")
      (node (ref "LED8") (pin "A") (pinfunction "A_A") (pintype "passive"))
      (node (ref "U$20") (pin "27") (pinfunction "P0_6_27") (pintype "bidirectional"))
    )
    (net (code "46") (name "Net-(U$20-P0_7)") (class "Default")
      (node (ref "LED7") (pin "A") (pinfunction "A_A") (pintype "passive"))
      (node (ref "U$20") (pin "26") (pinfunction "P0_7_26") (pintype "bidirectional"))
    )
    (net (code "47") (name "Net-(U$20-P1_7)") (class "Default")
      (node (ref "JP1") (pin "2") (pinfunction "2_2") (pintype "passive"))
      (node (ref "R60") (pin "1") (pinfunction "1_1") (pintype "passive"))
      (node (ref "U$20") (pin "12") (pinfunction "P1_7_12") (pintype "bidirectional"))
    )
    (net (code "48") (name "Net-(U$20-RESET#)") (class "Default")
      (node (ref "U$20") (pin "34") (pinfunction "RESET#_34") (pintype "bidirectional"))
      (node (ref "U$22") (pin "7") (pinfunction "7A_7") (pintype "bidirectional"))
    )
    (net (code "49") (name "Net-(U$25-CAP)") (class "Default")
      (node (ref "C41") (pin "2") (pinfunction "2_2") (pintype "passive"))
      (node (ref "U$25") (pin "2") (pinfunction "CAP_2") (pintype "bidirectional"))
    )
    (net (code "50") (name "Net-(U$26-D)") (class "Default")
      (node (ref "R35") (pin "2") (pinfunction "2_2") (pintype "passive"))
      (node (ref "U$26") (pin "3") (pinfunction "D_3") (pintype "bidirectional"))
    )
    (net (code "51") (name "Net-(U$26-G)") (class "Default")
      (node (ref "R16") (pin "2") (pinfunction "2_2") (pintype "passive"))
      (node (ref "U$26") (pin "1") (pinfunction "G_1") (pintype "bidirectional"))
    )
    (net (code "52") (name "Net-(U$26-S)") (class "Default")
      (node (ref "R51") (pin "1") (pinfunction "1_1") (pintype "passive"))
      (node (ref "U$26") (pin "2") (pinfunction "S_2") (pintype "bidirectional"))
      (node (ref "U$27") (pin "P$1") (pinfunction "P$1_P$1") (pintype "bidirectional"))
    )
    (net (code "53") (name "Net-(U$32-BYP)") (class "Default")
      (node (ref "C40") (pin "1") (pinfunction "1_1") (pintype "passive"))
      (node (ref "U$32") (pin "P$4") (pinfunction "BYP_P$4") (pintype "bidirectional"))
    )
    (net (code "54") (name "P2_1") (class "Default")
      (node (ref "U$20") (pin "10") (pinfunction "P2_1_10") (pintype "bidirectional"))
      (node (ref "U$22") (pin "4") (pinfunction "4A_4") (pintype "bidirectional"))
    )
    (net (code "55") (name "P2_2") (class "Default")
      (node (ref "U$20") (pin "9") (pinfunction "P2_2_9") (pintype "bidirectional"))
      (node (ref "U$22") (pin "3") (pinfunction "3A_3") (pintype "bidirectional"))
    )
    (net (code "56") (name "PACK+") (class "Default")
      (node (ref "C27") (pin "2") (pinfunction "2_2") (pintype "passive"))
      (node (ref "U$28") (pin "P$1") (pinfunction "P$1_P$1") (pintype "bidirectional"))
      (node (ref "U$29") (pin "2") (pinfunction "P$2_2") (pintype "bidirectional"))
      (node (ref "U$31") (pin "P$2") (pinfunction "2_P$2") (pintype "bidirectional"))
      (node (ref "U$35") (pin "P$1") (pinfunction "P$1_P$1") (pintype "bidirectional"))
      (node (ref "U$36") (pin "P$1") (pinfunction "P$1_P$1") (pintype "bidirectional"))
      (node (ref "U$39") (pin "P$1") (pinfunction "P$1_P$1") (pintype "bidirectional"))
    )
    (net (code "57") (name "PACK-") (class "Default")
      (node (ref "C18") (pin "1") (pinfunction "1_1") (pintype "passive"))
      (node (ref "C26") (pin "1") (pinfunction "1_1") (pintype "passive"))
      (node (ref "U$28") (pin "P$2") (pinfunction "P$2_P$2") (pintype "bidirectional"))
      (node (ref "U$29") (pin "1") (pinfunction "P$1_1") (pintype "bidirectional"))
      (node (ref "U$30") (pin "P$1") (pinfunction "P$1_P$1") (pintype "bidirectional"))
      (node (ref "U$38") (pin "P$1") (pinfunction "P$1_P$1") (pintype "bidirectional"))
      (node (ref "U$4") (pin "3") (pinfunction "D_3") (pintype "bidirectional"))
    )
    (net (code "58") (name "REGOUT") (class "Default")
      (node (ref "C28") (pin "1") (pinfunction "1_1") (pintype "passive"))
      (node (ref "C29") (pin "1") (pinfunction "1_1") (pintype "passive"))
      (node (ref "C30") (pin "1") (pinfunction "1_1") (pintype "passive"))
      (node (ref "C31") (pin "1") (pinfunction "1_1") (pintype "passive"))
      (node (ref "C32") (pin "1") (pinfunction "1_1") (pintype "passive"))
      (node (ref "C33") (pin "1") (pinfunction "1_1") (pintype "passive"))
      (node (ref "C38") (pin "1") (pinfunction "1_1") (pintype "passive"))
      (node (ref "C39") (pin "1") (pinfunction "1_1") (pintype "passive"))
      (node (ref "C42") (pin "2") (pinfunction "2_2") (pintype "passive"))
      (node (ref "C43") (pin "1") (pinfunction "1_1") (pintype "passive"))
      (node (ref "C44") (pin "2") (pinfunction "2_2") (pintype "passive"))
      (node (ref "JP1") (pin "1") (pinfunction "1_1") (pintype "passive"))
      (node (ref "R57") (pin "2") (pinfunction "2_2") (pintype "passive"))
      (node (ref "R58") (pin "2") (pinfunction "2_2") (pintype "passive"))
      (node (ref "U$1") (pin "8") (pinfunction "REGOUT_8") (pintype "bidirectional"))
      (node (ref "U$20") (pin "17") (pinfunction "DVDD_17") (pintype "bidirectional"))
      (node (ref "U$20") (pin "8") (pinfunction "AVDD_8") (pintype "bidirectional"))
      (node (ref "U$22") (pin "2") (pinfunction "2A_2") (pintype "bidirectional"))
      (node (ref "U$25") (pin "1") (pinfunction "VDD_1") (pintype "bidirectional"))
      (node (ref "U$25") (pin "4") (pinfunction "VDDIO_4") (pintype "bidirectional"))
      (node (ref "U$32") (pin "P$1") (pinfunction "VDD_P$1") (pintype "bidirectional"))
      (node (ref "U$32") (pin "P$8") (pinfunction "VDDIO_P$8") (pintype "bidirectional"))
      (node (ref "U$8") (pin "3") (pinfunction "D_3") (pintype "bidirectional"))
    )
    (net (code "59") (name "REGSRC") (class "Default")
      (node (ref "C25") (pin "2") (pinfunction "2_2") (pintype "passive"))
      (node (ref "R51") (pin "2") (pinfunction "2_2") (pintype "passive"))
      (node (ref "U$1") (pin "9") (pinfunction "REGSRC_9") (pintype "bidirectional"))
      (node (ref "U$27") (pin "P$2") (pinfunction "P$2_P$2") (pintype "bidirectional"))
    )
    (net (code "60") (name "SCL") (class "Default")
      (node (ref "JP5") (pin "2") (pinfunction "2_2") (pintype "passive"))
      (node (ref "R57") (pin "1") (pinfunction "1_1") (pintype "passive"))
      (node (ref "U$1") (pin "5") (pinfunction "SCL_5") (pintype "bidirectional"))
      (node (ref "U$20") (pin "14") (pinfunction "SCL_14") (pintype "bidirectional"))
      (node (ref "U$25") (pin "8") (pinfunction "SCL_8") (pintype "bidirectional"))
      (node (ref "U$32") (pin "P$2") (pinfunction "SCL_P$2") (pintype "bidirectional"))
    )
    (net (code "61") (name "SDA") (class "Default")
      (node (ref "JP5") (pin "3") (pinfunction "3_3") (pintype "passive"))
      (node (ref "R58") (pin "1") (pinfunction "1_1") (pintype "passive"))
      (node (ref "U$1") (pin "4") (pinfunction "SDA_4") (pintype "bidirectional"))
      (node (ref "U$20") (pin "15") (pinfunction "SDA_15") (pintype "bidirectional"))
      (node (ref "U$25") (pin "7") (pinfunction "SDA_7") (pintype "bidirectional"))
      (node (ref "U$32") (pin "P$10") (pinfunction "SDA_P$10") (pintype "bidirectional"))
    )
    (net (code "62") (name "VC5X") (class "Default")
      (node (ref "C1") (pin "1") (pinfunction "1_1") (pintype "passive"))
      (node (ref "C13") (pin "2") (pinfunction "2_2") (pintype "passive"))
      (node (ref "C19") (pin "1") (pinfunction "1_1") (pintype "passive"))
      (node (ref "C21") (pin "2") (pinfunction "2_2") (pintype "passive"))
      (node (ref "C8") (pin "1") (pinfunction "1_1") (pintype "passive"))
      (node (ref "R16") (pin "1") (pinfunction "1_1") (pintype "passive"))
      (node (ref "R20") (pin "2") (pinfunction "2_2") (pintype "passive"))
      (node (ref "R24") (pin "1") (pinfunction "1_1") (pintype "passive"))
      (node (ref "U$1") (pin "10") (pinfunction "VC5X_10") (pintype "bidirectional"))
      (node (ref "U$2") (pin "P$2") (pinfunction "P$2_P$2") (pintype "bidirectional"))
    )
    (net (code "63") (name "VC10X") (class "Default")
      (node (ref "C1") (pin "2") (pinfunction "2_2") (pintype "passive"))
      (node (ref "R30") (pin "1") (pinfunction "1_1") (pintype "passive"))
      (node (ref "U$1") (pin "15") (pinfunction "BAT_15") (pintype "bidirectional"))
      (node (ref "U$9") (pin "P$2") (pinfunction "P$2_P$2") (pintype "bidirectional"))
    )
    (net (code "64") (name "unconnected-(U$20-NC-Pad16)") (class "Default")
      (node (ref "U$20") (pin "16") (pinfunction "NC_16") (pintype "bidirectional"))
    )
    (net (code "65") (name "unconnected-(U$20-NC2-Pad35)") (class "Default")
      (node (ref "U$20") (pin "35") (pinfunction "NC2_35") (pintype "bidirectional"))
    )
    (net (code "66") (name "unconnected-(U$20-P0_0-Pad33)") (class "Default")
      (node (ref "U$20") (pin "33") (pinfunction "P0_0_33") (pintype "bidirectional"))
    )
    (net (code "67") (name "unconnected-(U$20-P0_1-Pad32)") (class "Default")
      (node (ref "U$20") (pin "32") (pinfunction "P0_1_32") (pintype "bidirectional"))
    )
    (net (code "68") (name "unconnected-(U$20-P0_2-Pad31)") (class "Default")
      (node (ref "U$20") (pin "31") (pinfunction "P0_2_31") (pintype "bidirectional"))
    )
    (net (code "69") (name "unconnected-(U$20-P0_3-Pad30)") (class "Default")
      (node (ref "U$20") (pin "30") (pinfunction "P0_3_30") (pintype "bidirectional"))
    )
    (net (code "70") (name "unconnected-(U$20-P0_4-Pad29)") (class "Default")
      (node (ref "U$20") (pin "29") (pinfunction "P0_4_29") (pintype "bidirectional"))
    )
    (net (code "71") (name "unconnected-(U$20-P0_5-Pad28)") (class "Default")
      (node (ref "U$20") (pin "28") (pinfunction "P0_5_28") (pintype "bidirectional"))
    )
    (net (code "72") (name "unconnected-(U$20-P1_0-Pad24)") (class "Default")
      (node (ref "U$20") (pin "24") (pinfunction "P1_0_24") (pintype "bidirectional"))
    )
    (net (code "73") (name "unconnected-(U$20-P1_2-Pad22)") (class "Default")
      (node (ref "U$20") (pin "22") (pinfunction "P1_2_22") (pintype "bidirectional"))
    )
    (net (code "74") (name "unconnected-(U$20-P1_3-Pad21)") (class "Default")
      (node (ref "U$20") (pin "21") (pinfunction "P1_3_21") (pintype "bidirectional"))
    )
    (net (code "75") (name "unconnected-(U$20-P1_4-Pad20)") (class "Default")
      (node (ref "U$20") (pin "20") (pinfunction "P1_4_20") (pintype "bidirectional"))
    )
    (net (code "76") (name "unconnected-(U$20-P1_6-Pad13)") (class "Default")
      (node (ref "U$20") (pin "13") (pinfunction "P1_6_13") (pintype "bidirectional"))
    )
    (net (code "77") (name "unconnected-(U$20-P2_0-Pad11)") (class "Default")
      (node (ref "U$20") (pin "11") (pinfunction "P2_0_11") (pintype "bidirectional"))
    )
    (net (code "78") (name "unconnected-(U$22-5A-Pad5)") (class "Default")
      (node (ref "U$22") (pin "5") (pinfunction "5A_5") (pintype "bidirectional"))
    )
    (net (code "79") (name "unconnected-(U$22-6A-Pad6)") (class "Default")
      (node (ref "U$22") (pin "6") (pinfunction "6A_6") (pintype "bidirectional"))
    )
    (net (code "80") (name "unconnected-(U$22-8A-Pad8)") (class "Default")
      (node (ref "U$22") (pin "8") (pinfunction "8A_8") (pintype "bidirectional"))
    )
    (net (code "81") (name "unconnected-(U$22-9A-Pad9)") (class "Default")
      (node (ref "U$22") (pin "9") (pinfunction "9A_9") (pintype "bidirectional"))
    )
    (net (code "82") (name "unconnected-(U$22-10A-Pad10)") (class "Default")
      (node (ref "U$22") (pin "10") (pinfunction "10A_10") (pintype "bidirectional"))
    )
    (net (code "83") (name "unconnected-(U$24-Pad6)") (class "Default")
      (node (ref "U$24") (pin "6") (pinfunction "6_6") (pintype "bidirectional"))
    )
    (net (code "84") (name "unconnected-(U$24-PadA1)") (class "Default")
      (node (ref "U$24") (pin "A1") (pinfunction "A1_A1") (pintype "bidirectional"))
    )
    (net (code "85") (name "unconnected-(U$24-PadA2)") (class "Default")
      (node (ref "U$24") (pin "A2") (pinfunction "A2_A2") (pintype "bidirectional"))
    )
    (net (code "86") (name "unconnected-(U$25-INT1-Pad6)") (class "Default")
      (node (ref "U$25") (pin "6") (pinfunction "INT1_6") (pintype "bidirectional"))
    )
    (net (code "87") (name "unconnected-(U$25-INT2-Pad5)") (class "Default")
      (node (ref "U$25") (pin "5") (pinfunction "INT2_5") (pintype "bidirectional"))
    )
    (net (code "88") (name "unconnected-(U$32-INT1-PadP$3)") (class "Default")
      (node (ref "U$32") (pin "P$3") (pinfunction "INT1_P$3") (pintype "bidirectional"))
    )
    (net (code "89") (name "unconnected-(U$32-INT2-PadP$5)") (class "Default")
      (node (ref "U$32") (pin "P$5") (pinfunction "INT2_P$5") (pintype "bidirectional"))
    )
    (net (code "90") (name "unconnected-(U$33-PadA1)") (class "Default")
      (node (ref "U$33") (pin "A1") (pinfunction "A1_A1") (pintype "bidirectional"))
    )
    (net (code "91") (name "unconnected-(U$33-PadA2)") (class "Default")
      (node (ref "U$33") (pin "A2") (pinfunction "A2_A2") (pintype "bidirectional"))
    )
  )
)
